# Analog.net
KiCad netlist of a schematic drawn in Altium Designer
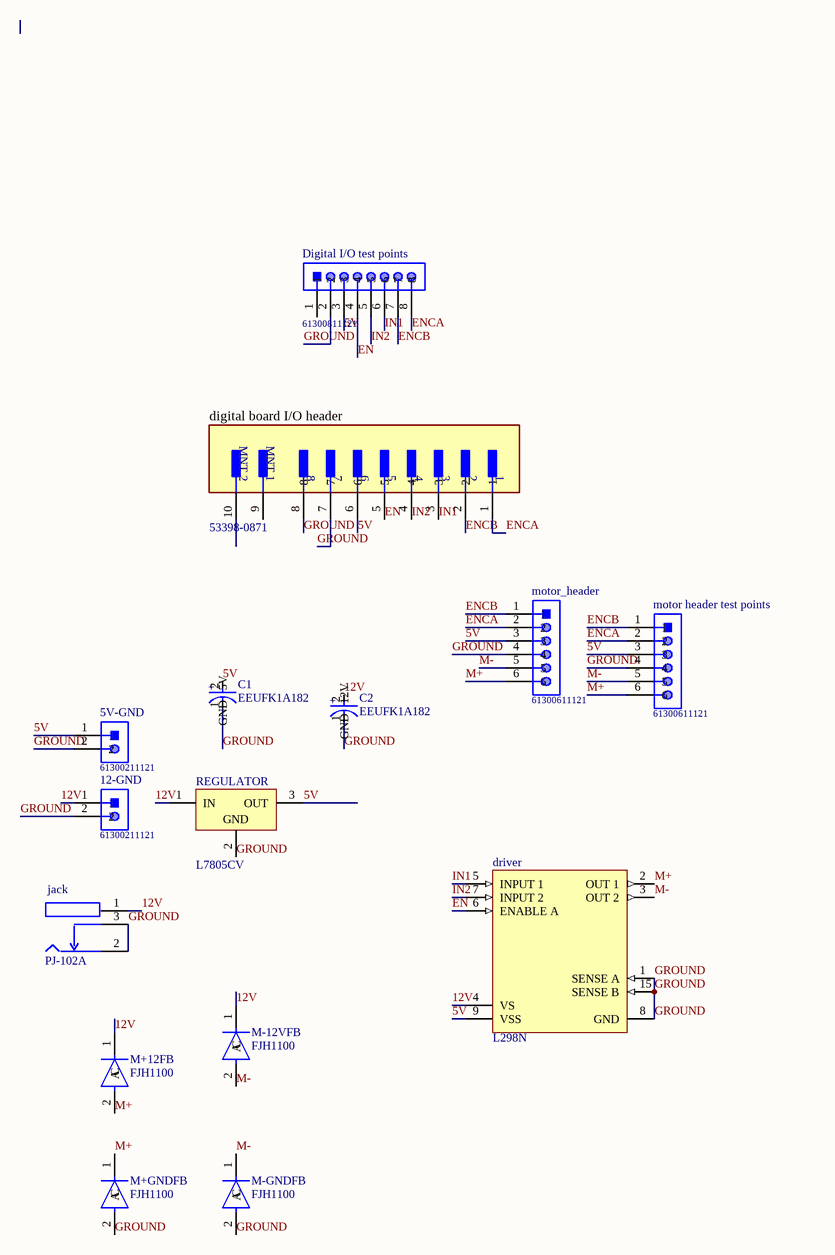
[diagram p0: Analog.SchDoc]

(export (version "E")
  (design (tool "Eeschema 10.0.6"))
  (components
    (comp (ref "5V-GND")
      (value "61300211121")
      (footprint "61300211121")
      (description "THT Vertical Pin Header WR-PHD, Pitch 2.54 mm, Single Row, 2 pins")
      (fields (field (name "MANUFACTURER") "Wurth Elektronik") (field (name "PUBLISHER") "WurthElektronik"))
      (libsource (lib "Altium Content Vault") (part "WE-CN-1P-M-R2"))
    )
    (comp (ref "12-GND")
      (value "61300211121")
      (footprint "61300211121")
      (description "THT Vertical Pin Header WR-PHD, Pitch 2.54 mm, Single Row, 2 pins")
      (fields (field (name "MANUFACTURER") "Wurth Elektronik") (field (name "PUBLISHER") "WurthElektronik"))
      (libsource (lib "Altium Content Vault") (part "WE-CN-1P-M-R2"))
    )
    (comp (ref "C1")
      (value "EEUFK1A182")
      (footprint "FP-RAD-TH-D_10_0_5-L_20_2-MFG")
      (description "Aluminum Electrolytic Capacitors (Radial Lead Type) AEC-Q200 Qualified 1800uF ±20% 10V")
      (fields (field (name "TOLERANCE") "20%") (field (name "VOLTAGE") "10V"))
      (libsource (lib "Altium Content Vault") (part "203bc49f2ac43e59fd269a8c329ed05"))
    )
    (comp (ref "C2")
      (value "EEUFK1A182")
      (footprint "FP-RAD-TH-D_10_0_5-L_20_2-MFG")
      (description "Aluminum Electrolytic Capacitors (Radial Lead Type) AEC-Q200 Qualified 1800uF ±20% 10V")
      (fields (field (name "TOLERANCE") "20%") (field (name "VOLTAGE") "10V"))
      (libsource (lib "Altium Content Vault") (part "203bc49f2ac43e59fd269a8c329ed05"))
    )
    (comp (ref "digital board I/O header")
      (value "53398-0871")
      (footprint "FP-53398-0871-MFG")
      (description "CONN HEADER SMD 8POS 1.25MM")
      (fields
        (field (name "MANUFACTURER") "Molex")
        (field (name "OCTOPART") "https://octopart.com/53398-0871-molex-655298")
      )
      (libsource (lib "Altium Content Vault") (part "98b5586d6b3804e276fbd0410cd4945"))
    )
    (comp (ref "Digital I/O test points")
      (value "61300811121")
      (footprint "61300811121")
      (description "THT Vertical Pin Header WR-PHD, Pitch 2.54 mm, Single Row, 8 pins")
      (fields (field (name "MANUFACTURER") "Wurth Elektronik") (field (name "PUBLISHER") "WurthElektronik"))
      (libsource (lib "Altium Content Vault") (part "WE-CN-1P-M-R8"))
    )
    (comp (ref "driver")
      (value "L298N")
      (footprint "STM-FM-15")
      (description "Dual Full-Bridge Driver, 4.8 to 46 V, -40 to 150 degC, 15-Pin FM (MW 15L), RoHS, Tube")
      (fields (field (name "MANUFACTURER") "STMicroelectronics") (field (name "PARTNUMBER") "L298"))
      (libsource (lib "Altium Content Vault") (part "STM-L298-15"))
    )
    (comp (ref "jack")
      (value "PJ-102A")
      (footprint "FP-PJ-102A-MFG")
      (description "CONN PWR JACK 2X5.5MM SOLDER")
      (fields (field (name "MANUFACTURER") "CUI") (field (name "VOLTAGE") "24V"))
      (libsource (lib "Altium Content Vault") (part "0685d7ee7311ef3291d1b1b03391b7d"))
    )
    (comp (ref "M+12FB")
      (value "FJH1100")
      (footprint "FP-017AG-MFG")
      (description "DIODE GEN PURP 15V 150MA DO35")
      (fields
        (field (name "OCTOPART") "https://octopart.com/fjh1100-on+semiconductor-84327057")
        (field (name "MANUFACTURER") "ON Semiconductor")
      )
      (libsource (lib "Altium Content Vault") (part "d7152d700b627762746794eb795d46e"))
    )
    (comp (ref "M+GNDFB")
      (value "FJH1100")
      (footprint "FP-017AG-MFG")
      (description "DIODE GEN PURP 15V 150MA DO35")
      (fields
        (field (name "OCTOPART") "https://octopart.com/fjh1100-on+semiconductor-84327057")
        (field (name "MANUFACTURER") "ON Semiconductor")
      )
      (libsource (lib "Altium Content Vault") (part "d7152d700b627762746794eb795d46e"))
    )
    (comp (ref "M-12VFB")
      (value "FJH1100")
      (footprint "FP-017AG-MFG")
      (description "DIODE GEN PURP 15V 150MA DO35")
      (fields
        (field (name "OCTOPART") "https://octopart.com/fjh1100-on+semiconductor-84327057")
        (field (name "MANUFACTURER") "ON Semiconductor")
      )
      (libsource (lib "Altium Content Vault") (part "d7152d700b627762746794eb795d46e"))
    )
    (comp (ref "M-GNDFB")
      (value "FJH1100")
      (footprint "FP-017AG-MFG")
      (description "DIODE GEN PURP 15V 150MA DO35")
      (fields
        (field (name "OCTOPART") "https://octopart.com/fjh1100-on+semiconductor-84327057")
        (field (name "MANUFACTURER") "ON Semiconductor")
      )
      (libsource (lib "Altium Content Vault") (part "d7152d700b627762746794eb795d46e"))
    )
    (comp (ref "motor header test points")
      (value "61300611121")
      (footprint "61300611121")
      (description "THT Vertical Pin Header WR-PHD, Pitch 2.54 mm, Single Row, 6 pins")
      (fields (field (name "MANUFACTURER") "Wurth Elektronik") (field (name "PUBLISHER") "WurthElektronik"))
      (libsource (lib "Altium Content Vault") (part "WE-CN-1P-M-R6"))
    )
    (comp (ref "motor_header")
      (value "61300611121")
      (footprint "61300611121")
      (description "THT Vertical Pin Header WR-PHD, Pitch 2.54 mm, Single Row, 6 pins")
      (fields (field (name "MANUFACTURER") "Wurth Elektronik") (field (name "PUBLISHER") "WurthElektronik"))
      (libsource (lib "Altium Content Vault") (part "WE-CN-1P-M-R6"))
    )
    (comp (ref "REGULATOR")
      (value "L7805CV")
      (footprint "TO220")
      (description "Positive Voltage Regulator, 5V, 3-Pin TO-220")
      (libsource (lib "Altium Content Vault") (part "PM-REG-L4940-SIL3"))
    )
  )
  (nets
    (net (code "1") (name "/5V") (class "Default")
      (node (ref "5V-GND") (pin "1") (pinfunction "1_1") (pintype "passive"))
      (node (ref "C1") (pin "2") (pinfunction "GND_2") (pintype "passive"))
      (node (ref "Digital I/O test points") (pin "3") (pinfunction "3_3") (pintype "passive"))
      (node (ref "REGULATOR") (pin "3") (pinfunction "OUT_3") (pintype "power_in"))
      (node (ref "digital board I/O header") (pin "6") (pinfunction "6_6") (pintype "passive"))
      (node (ref "driver") (pin "9") (pinfunction "VSS_9") (pintype "power_in"))
      (node (ref "motor header test points") (pin "3") (pinfunction "3_3") (pintype "passive"))
      (node (ref "motor_header") (pin "3") (pinfunction "3_3") (pintype "passive"))
    )
    (net (code "2") (name "/12V") (class "Default")
      (node (ref "12-GND") (pin "1") (pinfunction "1_1") (pintype "passive"))
      (node (ref "C2") (pin "2") (pinfunction "GND_2") (pintype "passive"))
      (node (ref "M+12FB") (pin "1") (pinfunction "C_1") (pintype "passive"))
      (node (ref "M-12VFB") (pin "1") (pinfunction "C_1") (pintype "passive"))
      (node (ref "REGULATOR") (pin "1") (pinfunction "IN_1") (pintype "power_in"))
      (node (ref "driver") (pin "4") (pinfunction "VS_4") (pintype "power_in"))
      (node (ref "jack") (pin "1") (pinfunction "1_1") (pintype "passive"))
    )
    (net (code "3") (name "/EN") (class "Default")
      (node (ref "Digital I/O test points") (pin "4") (pinfunction "4_4") (pintype "passive"))
      (node (ref "digital board I/O header") (pin "5") (pinfunction "5_5") (pintype "passive"))
      (node (ref "driver") (pin "6") (pinfunction "ENABLE_A_6") (pintype "input"))
    )
    (net (code "4") (name "/ENCA") (class "Default")
      (node (ref "Digital I/O test points") (pin "8") (pinfunction "8_8") (pintype "passive"))
      (node (ref "digital board I/O header") (pin "1") (pinfunction "1_1") (pintype "passive"))
      (node (ref "motor header test points") (pin "2") (pinfunction "2_2") (pintype "passive"))
      (node (ref "motor_header") (pin "2") (pinfunction "2_2") (pintype "passive"))
    )
    (net (code "5") (name "/ENCB") (class "Default")
      (node (ref "Digital I/O test points") (pin "7") (pinfunction "7_7") (pintype "passive"))
      (node (ref "digital board I/O header") (pin "2") (pinfunction "2_2") (pintype "passive"))
      (node (ref "motor header test points") (pin "1") (pinfunction "1_1") (pintype "passive"))
      (node (ref "motor_header") (pin "1") (pinfunction "1_1") (pintype "passive"))
    )
    (net (code "6") (name "/GROUND") (class "Default")
      (node (ref "12-GND") (pin "2") (pinfunction "2_2") (pintype "passive"))
      (node (ref "5V-GND") (pin "2") (pinfunction "2_2") (pintype "passive"))
      (node (ref "C1") (pin "1") (pinfunction "5V_1") (pintype "passive"))
      (node (ref "C2") (pin "1") (pinfunction "5V_1") (pintype "passive"))
      (node (ref "Digital I/O test points") (pin "2") (pinfunction "2_2") (pintype "passive"))
      (node (ref "M+GNDFB") (pin "2") (pinfunction "A_2") (pintype "passive"))
      (node (ref "M-GNDFB") (pin "2") (pinfunction "A_2") (pintype "passive"))
      (node (ref "REGULATOR") (pin "2") (pinfunction "GND_2") (pintype "power_in"))
      (node (ref "digital board I/O header") (pin "7") (pinfunction "7_7") (pintype "passive"))
      (node (ref "digital board I/O header") (pin "8") (pinfunction "8_8") (pintype "passive"))
      (node (ref "driver") (pin "1") (pinfunction "SENSE_A_1") (pintype "input"))
      (node (ref "driver") (pin "15") (pinfunction "SENSE_B_15") (pintype "input"))
      (node (ref "driver") (pin "8") (pinfunction "GND_8") (pintype "power_in"))
      (node (ref "jack") (pin "2") (pinfunction "2_2") (pintype "passive"))
      (node (ref "jack") (pin "3") (pinfunction "3_3") (pintype "passive"))
      (node (ref "motor header test points") (pin "4") (pinfunction "4_4") (pintype "passive"))
      (node (ref "motor_header") (pin "4") (pinfunction "4_4") (pintype "passive"))
    )
    (net (code "7") (name "/IN1") (class "Default")
      (node (ref "Digital I/O test points") (pin "6") (pinfunction "6_6") (pintype "passive"))
      (node (ref "digital board I/O header") (pin "3") (pinfunction "3_3") (pintype "passive"))
      (node (ref "driver") (pin "5") (pinfunction "INPUT_1_5") (pintype "input"))
    )
    (net (code "8") (name "/IN2") (class "Default")
      (node (ref "Digital I/O test points") (pin "5") (pinfunction "5_5") (pintype "passive"))
      (node (ref "digital board I/O header") (pin "4") (pinfunction "4_4") (pintype "passive"))
      (node (ref "driver") (pin "7") (pinfunction "INPUT_2_7") (pintype "input"))
    )
    (net (code "9") (name "/M+") (class "Default")
      (node (ref "M+12FB") (pin "2") (pinfunction "A_2") (pintype "passive"))
      (node (ref "M+GNDFB") (pin "1") (pinfunction "C_1") (pintype "passive"))
      (node (ref "driver") (pin "2") (pinfunction "OUT_1_2") (pintype "output"))
      (node (ref "motor header test points") (pin "6") (pinfunction "6_6") (pintype "passive"))
      (node (ref "motor_header") (pin "6") (pinfunction "6_6") (pintype "passive"))
    )
    (net (code "10") (name "/M-") (class "Default")
      (node (ref "M-12VFB") (pin "2") (pinfunction "A_2") (pintype "passive"))
      (node (ref "M-GNDFB") (pin "1") (pinfunction "C_1") (pintype "passive"))
      (node (ref "driver") (pin "3") (pinfunction "OUT_2_3") (pintype "output"))
      (node (ref "motor header test points") (pin "5") (pinfunction "5_5") (pintype "passive"))
      (node (ref "motor_header") (pin "5") (pinfunction "5_5") (pintype "passive"))
    )
    (net (code "11") (name "unconnected-(Digital I/O test points-Pad1)") (class "Default")
      (node (ref "Digital I/O test points") (pin "1") (pinfunction "1_1") (pintype "passive"))
    )
    (net (code "12") (name "unconnected-(digital board I/O header-MNT_1-Pad9)") (class "Default")
      (node (ref "digital board I/O header") (pin "9") (pinfunction "MNT_1_9") (pintype "passive"))
    )
    (net (code "13") (name "unconnected-(digital board I/O header-MNT_2-Pad10)") (class "Default")
      (node (ref "digital board I/O header") (pin "10") (pinfunction "MNT_2_10") (pintype "passive"))
    )
  )
)
